# untitled.net
KiCad netlist of a schematic drawn in EAGLE
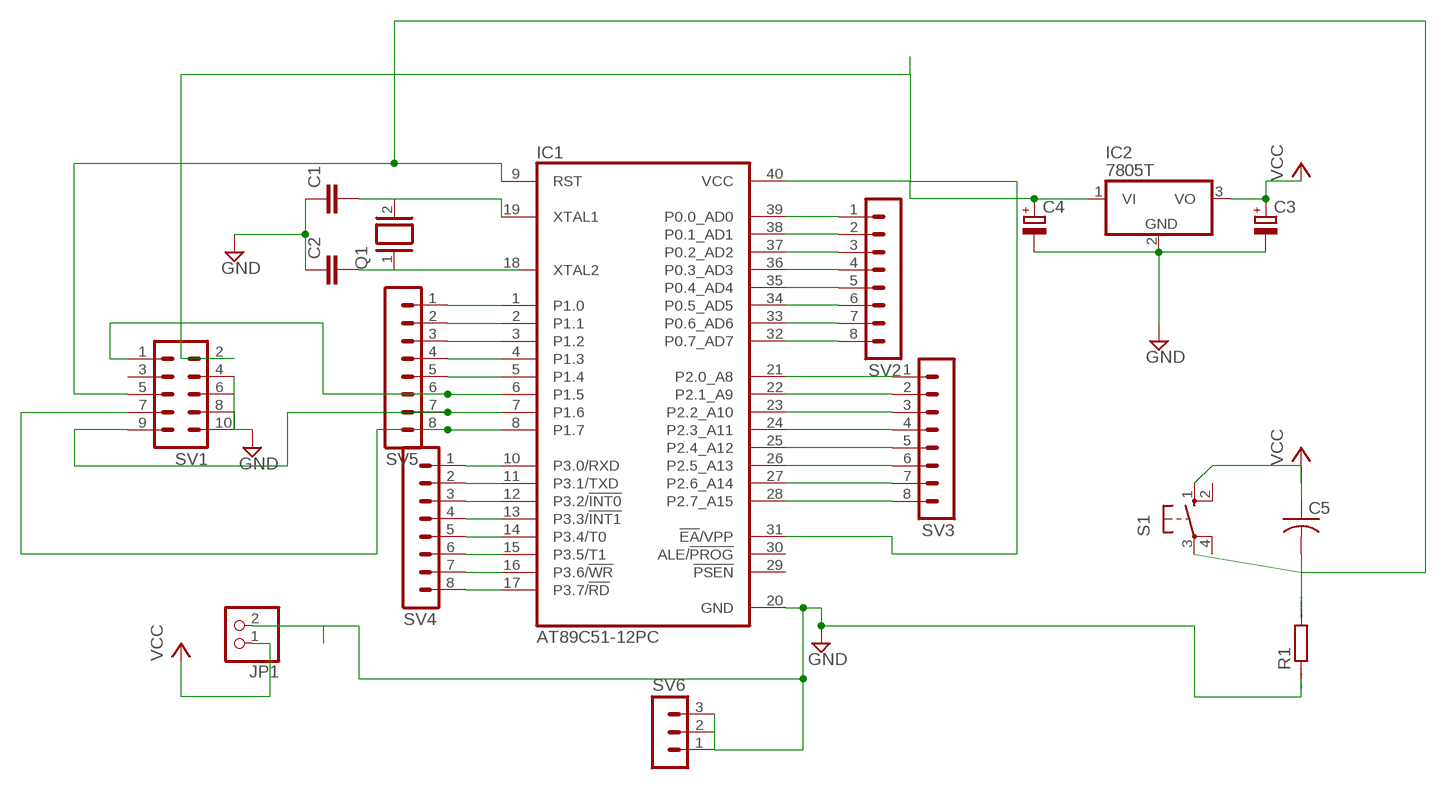
[diagram p0: schematic, sheet 1]

(export (version "E")
  (design (tool "Eeschema 10.0.6"))
  (components
    (comp (ref "C1")
      (value "C2,5-3")
      (footprint "eagle-import:C2.5-3")
      (libsource (lib "eagle-import") (part "C2,5-3"))
    )
    (comp (ref "C2")
      (value "C2,5-3")
      (footprint "eagle-import:C2.5-3")
      (libsource (lib "eagle-import") (part "C2,5-3"))
    )
    (comp (ref "C3")
      (value "CPOL-EUB45181A")
      (footprint "eagle-import:B45181A")
      (libsource (lib "eagle-import") (part "CPOL-EUB45181A"))
    )
    (comp (ref "C4")
      (value "CPOL-EUB45181A")
      (footprint "eagle-import:B45181A")
      (libsource (lib "eagle-import") (part "CPOL-EUB45181A"))
    )
    (comp (ref "C5")
      (value "C-US025-024X044")
      (footprint "eagle-import:C025-024X044")
      (libsource (lib "eagle-import") (part "C-US025-024X044"))
    )
    (comp (ref "IC1")
      (value "AT89C51-12PC")
      (footprint "eagle-import:DIL40")
      (libsource (lib "eagle-import") (part "AT89C51-PC12"))
    )
    (comp (ref "IC2")
      (value "7805T")
      (footprint "eagle-import:TO220H")
      (libsource (lib "eagle-import") (part "78T05"))
    )
    (comp (ref "JP1")
      (value "PINHD-1X2")
      (footprint "eagle-import:1X02")
      (libsource (lib "eagle-import") (part "PINHD-1X2"))
    )
    (comp (ref "Q1")
      (value "XTAL/S")
      (footprint "eagle-import:QS")
      (libsource (lib "eagle-import") (part "XTAL/S"))
    )
    (comp (ref "R1")
      (value "R0204/7")
      (footprint "eagle-import:0204_7")
      (libsource (lib "eagle-import") (part "R0204/7"))
    )
    (comp (ref "S1")
      (value "10-XX")
      (footprint "eagle-import:B3F-10XX")
      (fields (field (name "MPN") "B3F-1000"))
      (libsource (lib "eagle-import") (part "10-XX"))
    )
    (comp (ref "SV1")
      (value "MA05-2")
      (footprint "eagle-import:MA05-2")
      (libsource (lib "eagle-import") (part "MA05-2"))
    )
    (comp (ref "SV2")
      (value "MA08-1")
      (footprint "eagle-import:MA08-1")
      (libsource (lib "eagle-import") (part "MA08-1"))
    )
    (comp (ref "SV3")
      (value "MA08-1")
      (footprint "eagle-import:MA08-1")
      (libsource (lib "eagle-import") (part "MA08-1"))
    )
    (comp (ref "SV4")
      (value "MA08-1")
      (footprint "eagle-import:MA08-1")
      (libsource (lib "eagle-import") (part "MA08-1"))
    )
    (comp (ref "SV5")
      (value "MA08-1")
      (footprint "eagle-import:MA08-1")
      (libsource (lib "eagle-import") (part "MA08-1"))
    )
    (comp (ref "SV6")
      (value "MA03-1")
      (footprint "eagle-import:MA03-1")
      (libsource (lib "eagle-import") (part "MA03-1"))
    )
  )
  (nets
    (net (code "1") (name "GND") (class "Default")
      (node (ref "C1") (pin "1") (pinfunction "1_1") (pintype "passive"))
      (node (ref "C2") (pin "1") (pinfunction "1_1") (pintype "passive"))
      (node (ref "C3") (pin "-") (pinfunction "-_-") (pintype "passive"))
      (node (ref "C4") (pin "-") (pinfunction "-_-") (pintype "passive"))
      (node (ref "IC1") (pin "20") (pinfunction "GND_20") (pintype "power_in"))
      (node (ref "IC2") (pin "2") (pinfunction "GND_2") (pintype "passive"))
      (node (ref "JP1") (pin "2") (pinfunction "2_2") (pintype "passive"))
      (node (ref "R1") (pin "1") (pinfunction "1_1") (pintype "passive"))
      (node (ref "SV1") (pin "10") (pinfunction "10_10") (pintype "passive"))
      (node (ref "SV1") (pin "4") (pinfunction "4_4") (pintype "passive"))
      (node (ref "SV1") (pin "6") (pinfunction "6_6") (pintype "passive"))
      (node (ref "SV1") (pin "8") (pinfunction "8_8") (pintype "passive"))
      (node (ref "SV6") (pin "1") (pinfunction "1_1") (pintype "passive"))
      (node (ref "SV6") (pin "2") (pinfunction "2_2") (pintype "passive"))
      (node (ref "SV6") (pin "3") (pinfunction "3_3") (pintype "passive"))
    )
    (net (code "2") (name "Net-(IC1-P0.0_AD0)") (class "Default")
      (node (ref "IC1") (pin "39") (pinfunction "P0.0_AD0_39") (pintype "bidirectional"))
      (node (ref "SV2") (pin "1") (pinfunction "1_1") (pintype "passive"))
    )
    (net (code "3") (name "Net-(IC1-P0.1_AD1)") (class "Default")
      (node (ref "IC1") (pin "38") (pinfunction "P0.1_AD1_38") (pintype "bidirectional"))
      (node (ref "SV2") (pin "2") (pinfunction "2_2") (pintype "passive"))
    )
    (net (code "4") (name "Net-(IC1-P0.2_AD2)") (class "Default")
      (node (ref "IC1") (pin "37") (pinfunction "P0.2_AD2_37") (pintype "bidirectional"))
      (node (ref "SV2") (pin "3") (pinfunction "3_3") (pintype "passive"))
    )
    (net (code "5") (name "Net-(IC1-P0.3_AD3)") (class "Default")
      (node (ref "IC1") (pin "36") (pinfunction "P0.3_AD3_36") (pintype "bidirectional"))
      (node (ref "SV2") (pin "4") (pinfunction "4_4") (pintype "passive"))
    )
    (net (code "6") (name "Net-(IC1-P0.4_AD4)") (class "Default")
      (node (ref "IC1") (pin "35") (pinfunction "P0.4_AD4_35") (pintype "bidirectional"))
      (node (ref "SV2") (pin "5") (pinfunction "5_5") (pintype "passive"))
    )
    (net (code "7") (name "Net-(IC1-P0.5_AD5)") (class "Default")
      (node (ref "IC1") (pin "34") (pinfunction "P0.5_AD5_34") (pintype "bidirectional"))
      (node (ref "SV2") (pin "6") (pinfunction "6_6") (pintype "passive"))
    )
    (net (code "8") (name "Net-(IC1-P0.6_AD6)") (class "Default")
      (node (ref "IC1") (pin "33") (pinfunction "P0.6_AD6_33") (pintype "bidirectional"))
      (node (ref "SV2") (pin "7") (pinfunction "7_7") (pintype "passive"))
    )
    (net (code "9") (name "Net-(IC1-P0.7_AD7)") (class "Default")
      (node (ref "IC1") (pin "32") (pinfunction "P0.7_AD7_32") (pintype "bidirectional"))
      (node (ref "SV2") (pin "8") (pinfunction "8_8") (pintype "passive"))
    )
    (net (code "10") (name "Net-(IC1-P1.0)") (class "Default")
      (node (ref "IC1") (pin "1") (pinfunction "P1.0_1") (pintype "bidirectional"))
      (node (ref "SV5") (pin "1") (pinfunction "1_1") (pintype "passive"))
    )
    (net (code "11") (name "Net-(IC1-P1.1)") (class "Default")
      (node (ref "IC1") (pin "2") (pinfunction "P1.1_2") (pintype "bidirectional"))
      (node (ref "SV5") (pin "2") (pinfunction "2_2") (pintype "passive"))
    )
    (net (code "12") (name "Net-(IC1-P1.2)") (class "Default")
      (node (ref "IC1") (pin "3") (pinfunction "P1.2_3") (pintype "bidirectional"))
      (node (ref "SV5") (pin "3") (pinfunction "3_3") (pintype "passive"))
    )
    (net (code "13") (name "Net-(IC1-P1.3)") (class "Default")
      (node (ref "IC1") (pin "4") (pinfunction "P1.3_4") (pintype "bidirectional"))
      (node (ref "SV5") (pin "4") (pinfunction "4_4") (pintype "passive"))
    )
    (net (code "14") (name "Net-(IC1-P1.4)") (class "Default")
      (node (ref "IC1") (pin "5") (pinfunction "P1.4_5") (pintype "bidirectional"))
      (node (ref "SV5") (pin "5") (pinfunction "5_5") (pintype "passive"))
    )
    (net (code "15") (name "Net-(IC1-P1.5)") (class "Default")
      (node (ref "IC1") (pin "6") (pinfunction "P1.5_6") (pintype "bidirectional"))
      (node (ref "SV1") (pin "1") (pinfunction "1_1") (pintype "passive"))
      (node (ref "SV5") (pin "6") (pinfunction "6_6") (pintype "passive"))
    )
    (net (code "16") (name "Net-(IC1-P1.6)") (class "Default")
      (node (ref "IC1") (pin "7") (pinfunction "P1.6_7") (pintype "bidirectional"))
      (node (ref "SV1") (pin "9") (pinfunction "9_9") (pintype "passive"))
      (node (ref "SV5") (pin "7") (pinfunction "7_7") (pintype "passive"))
    )
    (net (code "17") (name "Net-(IC1-P1.7)") (class "Default")
      (node (ref "IC1") (pin "8") (pinfunction "P1.7_8") (pintype "bidirectional"))
      (node (ref "SV1") (pin "7") (pinfunction "7_7") (pintype "passive"))
      (node (ref "SV5") (pin "8") (pinfunction "8_8") (pintype "passive"))
    )
    (net (code "18") (name "Net-(IC1-P2.0_A8)") (class "Default")
      (node (ref "IC1") (pin "21") (pinfunction "P2.0_A8_21") (pintype "bidirectional"))
      (node (ref "SV3") (pin "1") (pinfunction "1_1") (pintype "passive"))
    )
    (net (code "19") (name "Net-(IC1-P2.1_A9)") (class "Default")
      (node (ref "IC1") (pin "22") (pinfunction "P2.1_A9_22") (pintype "bidirectional"))
      (node (ref "SV3") (pin "2") (pinfunction "2_2") (pintype "passive"))
    )
    (net (code "20") (name "Net-(IC1-P2.2_A10)") (class "Default")
      (node (ref "IC1") (pin "23") (pinfunction "P2.2_A10_23") (pintype "bidirectional"))
      (node (ref "SV3") (pin "3") (pinfunction "3_3") (pintype "passive"))
    )
    (net (code "21") (name "Net-(IC1-P2.3_A11)") (class "Default")
      (node (ref "IC1") (pin "24") (pinfunction "P2.3_A11_24") (pintype "bidirectional"))
      (node (ref "SV3") (pin "4") (pinfunction "4_4") (pintype "passive"))
    )
    (net (code "22") (name "Net-(IC1-P2.4_A12)") (class "Default")
      (node (ref "IC1") (pin "25") (pinfunction "P2.4_A12_25") (pintype "bidirectional"))
      (node (ref "SV3") (pin "5") (pinfunction "5_5") (pintype "passive"))
    )
    (net (code "23") (name "Net-(IC1-P2.5_A13)") (class "Default")
      (node (ref "IC1") (pin "26") (pinfunction "P2.5_A13_26") (pintype "bidirectional"))
      (node (ref "SV3") (pin "6") (pinfunction "6_6") (pintype "passive"))
    )
    (net (code "24") (name "Net-(IC1-P2.6_A14)") (class "Default")
      (node (ref "IC1") (pin "27") (pinfunction "P2.6_A14_27") (pintype "bidirectional"))
      (node (ref "SV3") (pin "7") (pinfunction "7_7") (pintype "passive"))
    )
    (net (code "25") (name "Net-(IC1-P2.7_A15)") (class "Default")
      (node (ref "IC1") (pin "28") (pinfunction "P2.7_A15_28") (pintype "bidirectional"))
      (node (ref "SV3") (pin "8") (pinfunction "8_8") (pintype "passive"))
    )
    (net (code "26") (name "Net-(IC1-P3.0{slash}RXD)") (class "Default")
      (node (ref "IC1") (pin "10") (pinfunction "P3.0/RXD_10") (pintype "bidirectional"))
      (node (ref "SV4") (pin "1") (pinfunction "1_1") (pintype "passive"))
    )
    (net (code "27") (name "Net-(IC1-P3.1{slash}TXD)") (class "Default")
      (node (ref "IC1") (pin "11") (pinfunction "P3.1/TXD_11") (pintype "bidirectional"))
      (node (ref "SV4") (pin "2") (pinfunction "2_2") (pintype "passive"))
    )
    (net (code "28") (name "Net-(IC1-P3.2{slash}~{INT0})") (class "Default")
      (node (ref "IC1") (pin "12") (pinfunction "P3.2/~{INT0}_12") (pintype "bidirectional"))
      (node (ref "SV4") (pin "3") (pinfunction "3_3") (pintype "passive"))
    )
    (net (code "29") (name "Net-(IC1-P3.3{slash}~{INT1})") (class "Default")
      (node (ref "IC1") (pin "13") (pinfunction "P3.3/~{INT1}_13") (pintype "bidirectional"))
      (node (ref "SV4") (pin "4") (pinfunction "4_4") (pintype "passive"))
    )
    (net (code "30") (name "Net-(IC1-P3.4{slash}T0)") (class "Default")
      (node (ref "IC1") (pin "14") (pinfunction "P3.4/T0_14") (pintype "bidirectional"))
      (node (ref "SV4") (pin "5") (pinfunction "5_5") (pintype "passive"))
    )
    (net (code "31") (name "Net-(IC1-P3.5{slash}T1)") (class "Default")
      (node (ref "IC1") (pin "15") (pinfunction "P3.5/T1_15") (pintype "bidirectional"))
      (node (ref "SV4") (pin "6") (pinfunction "6_6") (pintype "passive"))
    )
    (net (code "32") (name "Net-(IC1-P3.6{slash}~{WR})") (class "Default")
      (node (ref "IC1") (pin "16") (pinfunction "P3.6/~{WR}_16") (pintype "bidirectional"))
      (node (ref "SV4") (pin "7") (pinfunction "7_7") (pintype "passive"))
    )
    (net (code "33") (name "Net-(IC1-P3.7{slash}~{RD})") (class "Default")
      (node (ref "IC1") (pin "17") (pinfunction "P3.7/~{RD}_17") (pintype "bidirectional"))
      (node (ref "SV4") (pin "8") (pinfunction "8_8") (pintype "passive"))
    )
    (net (code "34") (name "Net-(IC1-RST)") (class "Default")
      (node (ref "C5") (pin "2") (pinfunction "2_2") (pintype "passive"))
      (node (ref "IC1") (pin "9") (pinfunction "RST_9") (pintype "input"))
      (node (ref "R1") (pin "2") (pinfunction "2_2") (pintype "passive"))
      (node (ref "S1") (pin "3") (pinfunction "P_3") (pintype "passive"))
      (node (ref "SV1") (pin "5") (pinfunction "5_5") (pintype "passive"))
    )
    (net (code "35") (name "Net-(IC1-VCC)") (class "Default")
      (node (ref "C4") (pin "+") (pinfunction "+_+") (pintype "passive"))
      (node (ref "IC1") (pin "31") (pinfunction "~{EA}/VPP_31") (pintype "input"))
      (node (ref "IC1") (pin "40") (pinfunction "VCC_40") (pintype "power_in"))
      (node (ref "IC2") (pin "1") (pinfunction "VI_1") (pintype "input"))
      (node (ref "SV1") (pin "2") (pinfunction "2_2") (pintype "passive"))
    )
    (net (code "36") (name "Net-(IC1-XTAL1)") (class "Default")
      (node (ref "C1") (pin "2") (pinfunction "2_2") (pintype "passive"))
      (node (ref "IC1") (pin "19") (pinfunction "XTAL1_19") (pintype "input"))
      (node (ref "Q1") (pin "2") (pinfunction "2_2") (pintype "passive"))
    )
    (net (code "37") (name "Net-(IC1-XTAL2)") (class "Default")
      (node (ref "C2") (pin "2") (pinfunction "2_2") (pintype "passive"))
      (node (ref "IC1") (pin "18") (pinfunction "XTAL2_18") (pintype "input"))
      (node (ref "Q1") (pin "1") (pinfunction "1_1") (pintype "passive"))
    )
    (net (code "38") (name "VCC") (class "Default")
      (node (ref "C3") (pin "+") (pinfunction "+_+") (pintype "passive"))
      (node (ref "C5") (pin "1") (pinfunction "1_1") (pintype "passive"))
      (node (ref "IC2") (pin "3") (pinfunction "VO_3") (pintype "passive"))
      (node (ref "JP1") (pin "1") (pinfunction "1_1") (pintype "passive"))
      (node (ref "S1") (pin "1") (pinfunction "S_1") (pintype "passive"))
    )
    (net (code "39") (name "unconnected-(IC1-ALE{slash}~{PROG}-Pad30)") (class "Default")
      (node (ref "IC1") (pin "30") (pinfunction "ALE/~{PROG}_30") (pintype "output"))
    )
    (net (code "40") (name "unconnected-(IC1-~{PSEN}-Pad29)") (class "Default")
      (node (ref "IC1") (pin "29") (pinfunction "~{PSEN}_29") (pintype "output"))
    )
    (net (code "41") (name "unconnected-(S1-P1-Pad4)") (class "Default")
      (node (ref "S1") (pin "4") (pinfunction "P1_4") (pintype "passive"))
    )
    (net (code "42") (name "unconnected-(S1-S1-Pad2)") (class "Default")
      (node (ref "S1") (pin "2") (pinfunction "S1_2") (pintype "passive"))
    )
    (net (code "43") (name "unconnected-(SV1-Pad3)") (class "Default")
      (node (ref "SV1") (pin "3") (pinfunction "3_3") (pintype "passive"))
    )
  )
)
